# uC.net
KiCad netlist of a schematic drawn in Altium Designer
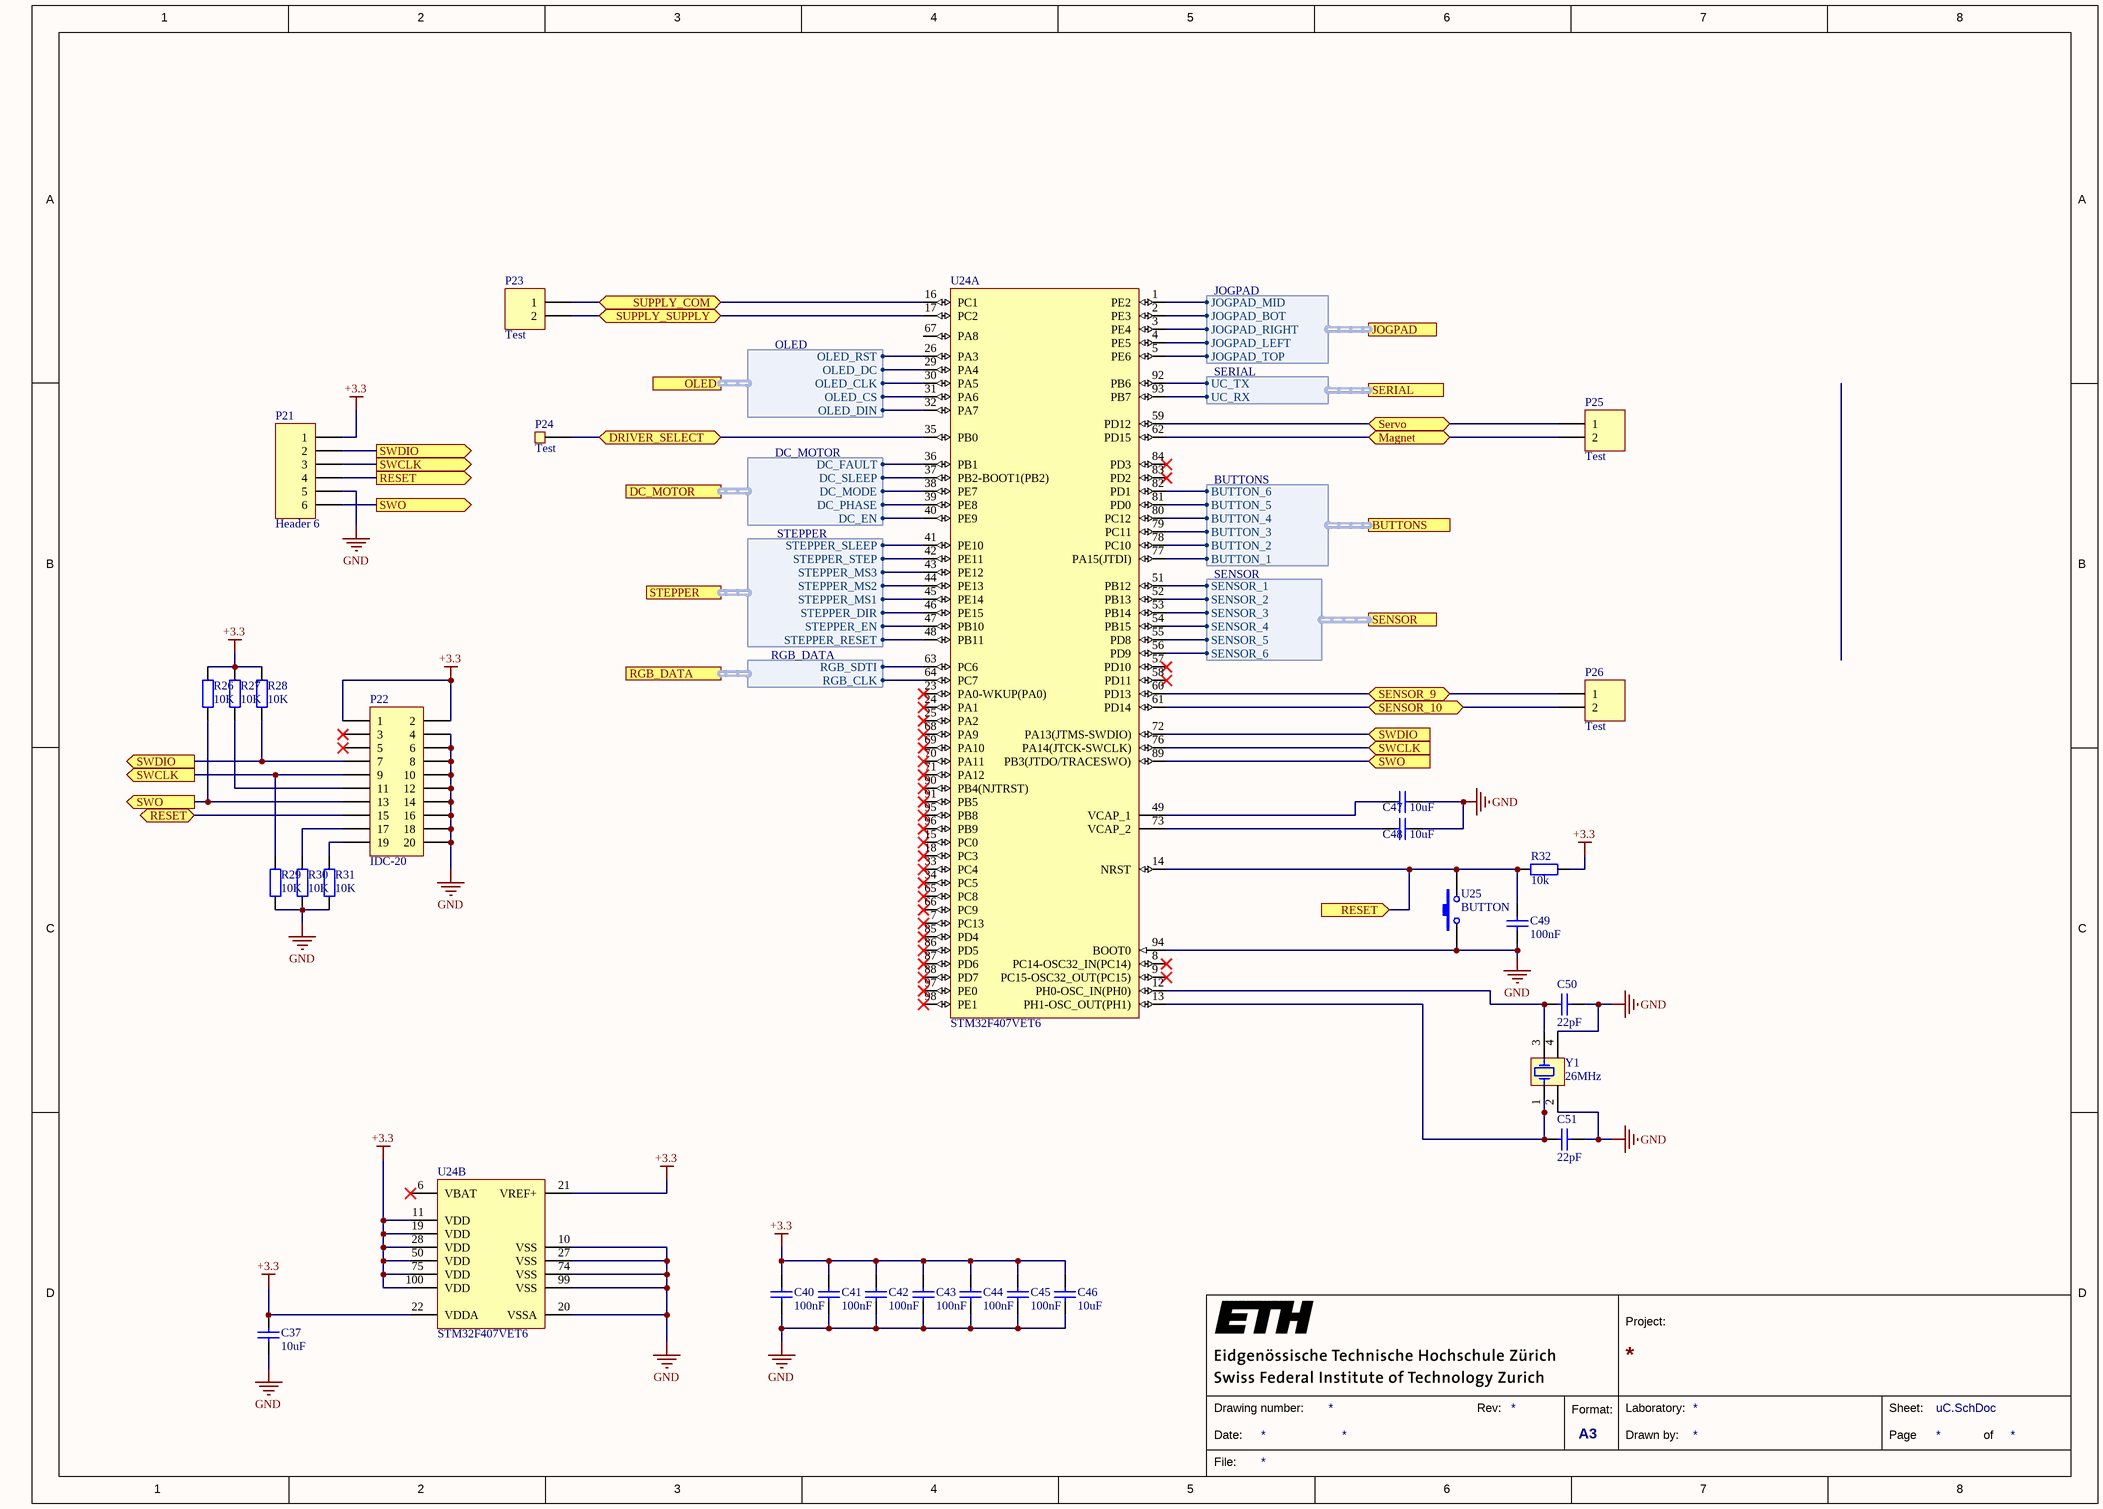
[diagram p0: uC.SchDoc]

(export (version "E")
  (design (tool "Eeschema 10.0.6"))
  (components
    (comp (ref "C37")
      (value "10uF")
      (footprint "CAP_0603i_1608m -N")
      (description "capacitor")
      (libsource (lib "IDSC std generic parts") (part "Cap"))
    )
    (comp (ref "C40")
      (value "100nF")
      (footprint "CAP_0402i_1005m -N")
      (description "capacitor")
      (libsource (lib "IDSC std generic parts") (part "Cap"))
    )
    (comp (ref "C41")
      (value "100nF")
      (footprint "CAP_0402i_1005m -N")
      (description "capacitor")
      (libsource (lib "IDSC std generic parts") (part "Cap"))
    )
    (comp (ref "C42")
      (value "100nF")
      (footprint "CAP_0402i_1005m -N")
      (description "capacitor")
      (libsource (lib "IDSC std generic parts") (part "Cap"))
    )
    (comp (ref "C43")
      (value "100nF")
      (footprint "CAP_0402i_1005m -N")
      (description "capacitor")
      (libsource (lib "IDSC std generic parts") (part "Cap"))
    )
    (comp (ref "C44")
      (value "100nF")
      (footprint "CAP_0402i_1005m -N")
      (description "capacitor")
      (libsource (lib "IDSC std generic parts") (part "Cap"))
    )
    (comp (ref "C45")
      (value "100nF")
      (footprint "CAP_0402i_1005m -N")
      (description "capacitor")
      (libsource (lib "IDSC std generic parts") (part "Cap"))
    )
    (comp (ref "C46")
      (value "10uF")
      (footprint "CAP_0603i_1608m -N")
      (description "capacitor")
      (libsource (lib "IDSC std generic parts") (part "Cap"))
    )
    (comp (ref "C47")
      (value "10uF")
      (footprint "CAP_0603i_1608m -N")
      (description "capacitor")
      (libsource (lib "IDSC std generic parts") (part "Cap"))
    )
    (comp (ref "C48")
      (value "10uF")
      (footprint "CAP_0603i_1608m -N")
      (description "capacitor")
      (libsource (lib "IDSC std generic parts") (part "Cap"))
    )
    (comp (ref "C49")
      (value "100nF")
      (footprint "CAP_0402i_1005m -N")
      (description "capacitor")
      (libsource (lib "IDSC std generic parts") (part "Cap"))
    )
    (comp (ref "C50")
      (value "22pF")
      (footprint "CAP_0603i_1608m -N")
      (description "capacitor")
      (libsource (lib "IDSC std generic parts") (part "Cap"))
    )
    (comp (ref "C51")
      (value "22pF")
      (footprint "CAP_0603i_1608m -N")
      (description "capacitor")
      (libsource (lib "IDSC std generic parts") (part "Cap"))
    )
    (comp (ref "P21")
      (value "Header 6")
      (footprint "HDR1X6")
      (description "Header, 6-Pin")
      (libsource (lib "IDSC std connectors") (part "Header 6"))
    )
    (comp (ref "P22")
      (value "IDC-20")
      (footprint "IDC-20")
      (description "Connector; IDC, Male Header, Thru-Hole; 20 Position; Vertical; Pitch 2.54 mm; B")
      (libsource (lib "IDSC std connectors") (part "IDC-20"))
    )
    (comp (ref "P23")
      (value "Test")
      (footprint "HDR1X2")
      (description "Header, 2-Pin")
      (libsource (lib "") (part "Header 2_1"))
    )
    (comp (ref "P24")
      (value "Test")
      (footprint "PIN1")
      (description "Single Pad or Testpoint")
      (libsource (lib "IDSC std connectors") (part "Pad"))
    )
    (comp (ref "P25")
      (value "Test")
      (footprint "HDR1X2")
      (description "Header, 2-Pin")
      (libsource (lib "IDSC std connectors") (part "Header 2"))
    )
    (comp (ref "P26")
      (value "Test")
      (footprint "HDR1X2")
      (description "Header, 2-Pin")
      (libsource (lib "IDSC std connectors") (part "Header 2"))
    )
    (comp (ref "R26")
      (value "10K")
      (footprint "RES_0603i_1608m -N")
      (description "Resistor")
      (libsource (lib "IDSC std generic parts") (part "Res"))
    )
    (comp (ref "R27")
      (value "10K")
      (footprint "RES_0603i_1608m -N")
      (description "Resistor")
      (libsource (lib "IDSC std generic parts") (part "Res"))
    )
    (comp (ref "R28")
      (value "10K")
      (footprint "RES_0603i_1608m -N")
      (description "Resistor")
      (libsource (lib "IDSC std generic parts") (part "Res"))
    )
    (comp (ref "R29")
      (value "10K")
      (footprint "RES_0603i_1608m -N")
      (description "Resistor")
      (libsource (lib "IDSC std generic parts") (part "Res"))
    )
    (comp (ref "R30")
      (value "10K")
      (footprint "RES_0603i_1608m -N")
      (description "Resistor")
      (libsource (lib "IDSC std generic parts") (part "Res"))
    )
    (comp (ref "R31")
      (value "10K")
      (footprint "RES_0603i_1608m -N")
      (description "Resistor")
      (libsource (lib "IDSC std generic parts") (part "Res"))
    )
    (comp (ref "R32")
      (value "10k")
      (footprint "RES_0603i_1608m -N")
      (description "Resistor")
      (libsource (lib "") (part "Res_1"))
    )
    (comp (ref "U24")
      (value "STM32F407VET6")
      (footprint "STM-LQFP100_M")
      (fields (field (name "MANUFACTURER") "STMicroelectronics"))
      (libsource (lib "Altium Content Vault") (part "MC-ARM-STM32F40X_41X-SQ100"))
    )
    (comp (ref "U25")
      (value "BUTTON")
      (footprint "RND 210-00206")
      (libsource (lib "BMA_lib") (part "BUTTON"))
    )
    (comp (ref "Y1")
      (value "26MHz")
      (footprint "TSX-3225 2*2.5")
      (description "Industrial Ceramic Resonator")
      (libsource (lib "IDSC std generic parts") (part "XTAL3"))
    )
  )
  (nets
    (net (code "9") (name "+3.3") (class "Default")
      (node (ref "C37") (pin "2") (pinfunction "2_2") (pintype "passive"))
      (node (ref "C40") (pin "1") (pinfunction "1_1") (pintype "passive"))
      (node (ref "C41") (pin "2") (pinfunction "2_2") (pintype "passive"))
      (node (ref "C42") (pin "2") (pinfunction "2_2") (pintype "passive"))
      (node (ref "C43") (pin "2") (pinfunction "2_2") (pintype "passive"))
      (node (ref "C44") (pin "2") (pinfunction "2_2") (pintype "passive"))
      (node (ref "C45") (pin "2") (pinfunction "2_2") (pintype "passive"))
      (node (ref "C46") (pin "2") (pinfunction "2_2") (pintype "passive"))
      (node (ref "P21") (pin "1") (pinfunction "1_1") (pintype "passive"))
      (node (ref "P22") (pin "1") (pinfunction "1_1") (pintype "passive"))
      (node (ref "P22") (pin "2") (pinfunction "2_2") (pintype "passive"))
      (node (ref "R26") (pin "2") (pinfunction "2_2") (pintype "passive"))
      (node (ref "R27") (pin "2") (pinfunction "2_2") (pintype "passive"))
      (node (ref "R28") (pin "2") (pinfunction "2_2") (pintype "passive"))
      (node (ref "R32") (pin "1") (pinfunction "1_1") (pintype "passive"))
      (node (ref "U24") (pin "100") (pinfunction "VDD_100") (pintype "power_in"))
      (node (ref "U24") (pin "11") (pinfunction "VDD_11") (pintype "power_in"))
      (node (ref "U24") (pin "19") (pinfunction "VDD_19") (pintype "power_in"))
      (node (ref "U24") (pin "21") (pinfunction "VREF+_21") (pintype "power_in"))
      (node (ref "U24") (pin "22") (pinfunction "VDDA_22") (pintype "power_in"))
      (node (ref "U24") (pin "28") (pinfunction "VDD_28") (pintype "power_in"))
      (node (ref "U24") (pin "50") (pinfunction "VDD_50") (pintype "power_in"))
      (node (ref "U24") (pin "75") (pinfunction "VDD_75") (pintype "power_in"))
    )
    (net (code "10") (name "/BUTTON_1") (class "Default")
      (node (ref "U24") (pin "77") (pinfunction "PA15(JTDI)_77") (pintype "bidirectional"))
    )
    (net (code "11") (name "/BUTTON_2") (class "Default")
      (node (ref "U24") (pin "78") (pinfunction "PC10_78") (pintype "bidirectional"))
    )
    (net (code "12") (name "/BUTTON_3") (class "Default")
      (node (ref "U24") (pin "79") (pinfunction "PC11_79") (pintype "bidirectional"))
    )
    (net (code "13") (name "/BUTTON_4") (class "Default")
      (node (ref "U24") (pin "80") (pinfunction "PC12_80") (pintype "bidirectional"))
    )
    (net (code "14") (name "/BUTTON_5") (class "Default")
      (node (ref "U24") (pin "81") (pinfunction "PD0_81") (pintype "bidirectional"))
    )
    (net (code "15") (name "/BUTTON_6") (class "Default")
      (node (ref "U24") (pin "82") (pinfunction "PD1_82") (pintype "bidirectional"))
    )
    (net (code "16") (name "/DC_EN") (class "Default")
      (node (ref "U24") (pin "40") (pinfunction "PE9_40") (pintype "bidirectional"))
    )
    (net (code "17") (name "/DC_FAULT") (class "Default")
      (node (ref "U24") (pin "36") (pinfunction "PB1_36") (pintype "bidirectional"))
    )
    (net (code "18") (name "/DC_MODE") (class "Default")
      (node (ref "U24") (pin "38") (pinfunction "PE7_38") (pintype "bidirectional"))
    )
    (net (code "19") (name "/DC_PHASE") (class "Default")
      (node (ref "U24") (pin "39") (pinfunction "PE8_39") (pintype "bidirectional"))
    )
    (net (code "20") (name "/DC_SLEEP") (class "Default")
      (node (ref "U24") (pin "37") (pinfunction "PB2-BOOT1(PB2)_37") (pintype "bidirectional"))
    )
    (net (code "21") (name "/DRIVER_SELECT") (class "Default")
      (node (ref "P24") (pin "1") (pinfunction "1_1") (pintype "passive"))
      (node (ref "U24") (pin "35") (pinfunction "PB0_35") (pintype "bidirectional"))
    )
    (net (code "22") (name "/JOGPAD_BOT") (class "Default")
      (node (ref "U24") (pin "2") (pinfunction "PE3_2") (pintype "bidirectional"))
    )
    (net (code "23") (name "/JOGPAD_LEFT") (class "Default")
      (node (ref "U24") (pin "4") (pinfunction "PE5_4") (pintype "bidirectional"))
    )
    (net (code "24") (name "/JOGPAD_MID") (class "Default")
      (node (ref "U24") (pin "1") (pinfunction "PE2_1") (pintype "bidirectional"))
    )
    (net (code "25") (name "/JOGPAD_RIGHT") (class "Default")
      (node (ref "U24") (pin "3") (pinfunction "PE4_3") (pintype "bidirectional"))
    )
    (net (code "26") (name "/JOGPAD_TOP") (class "Default")
      (node (ref "U24") (pin "5") (pinfunction "PE6_5") (pintype "bidirectional"))
    )
    (net (code "27") (name "/Magnet") (class "Default")
      (node (ref "P25") (pin "2") (pinfunction "2_2") (pintype "passive"))
      (node (ref "U24") (pin "62") (pinfunction "PD15_62") (pintype "bidirectional"))
    )
    (net (code "28") (name "/OLED_CLK") (class "Default")
      (node (ref "U24") (pin "30") (pinfunction "PA5_30") (pintype "bidirectional"))
    )
    (net (code "29") (name "/OLED_CS") (class "Default")
      (node (ref "U24") (pin "31") (pinfunction "PA6_31") (pintype "bidirectional"))
    )
    (net (code "30") (name "/OLED_DC") (class "Default")
      (node (ref "U24") (pin "29") (pinfunction "PA4_29") (pintype "bidirectional"))
    )
    (net (code "31") (name "/OLED_DIN") (class "Default")
      (node (ref "U24") (pin "32") (pinfunction "PA7_32") (pintype "bidirectional"))
    )
    (net (code "32") (name "/OLED_RST") (class "Default")
      (node (ref "U24") (pin "26") (pinfunction "PA3_26") (pintype "bidirectional"))
    )
    (net (code "33") (name "/RESET") (class "Default")
      (node (ref "C49") (pin "2") (pinfunction "2_2") (pintype "passive"))
      (node (ref "P21") (pin "4") (pinfunction "4_4") (pintype "passive"))
      (node (ref "P22") (pin "15") (pinfunction "15_15") (pintype "passive"))
      (node (ref "R32") (pin "2") (pinfunction "2_2") (pintype "passive"))
      (node (ref "U24") (pin "14") (pinfunction "NRST_14") (pintype "bidirectional"))
      (node (ref "U25") (pin "2") (pinfunction "2_2") (pintype "passive"))
    )
    (net (code "34") (name "/RGB_CLK") (class "Default")
      (node (ref "U24") (pin "64") (pinfunction "PC7_64") (pintype "bidirectional"))
    )
    (net (code "35") (name "/RGB_SDTI") (class "Default")
      (node (ref "U24") (pin "63") (pinfunction "PC6_63") (pintype "bidirectional"))
    )
    (net (code "36") (name "/SENSOR_1") (class "Default")
      (node (ref "U24") (pin "51") (pinfunction "PB12_51") (pintype "bidirectional"))
    )
    (net (code "37") (name "/SENSOR_2") (class "Default")
      (node (ref "U24") (pin "52") (pinfunction "PB13_52") (pintype "bidirectional"))
    )
    (net (code "38") (name "/SENSOR_3") (class "Default")
      (node (ref "U24") (pin "53") (pinfunction "PB14_53") (pintype "bidirectional"))
    )
    (net (code "39") (name "/SENSOR_4") (class "Default")
      (node (ref "U24") (pin "54") (pinfunction "PB15_54") (pintype "bidirectional"))
    )
    (net (code "40") (name "/SENSOR_5") (class "Default")
      (node (ref "U24") (pin "55") (pinfunction "PD8_55") (pintype "bidirectional"))
    )
    (net (code "41") (name "/SENSOR_6") (class "Default")
      (node (ref "U24") (pin "56") (pinfunction "PD9_56") (pintype "bidirectional"))
    )
    (net (code "42") (name "/SENSOR_9") (class "Default")
      (node (ref "P26") (pin "1") (pinfunction "1_1") (pintype "passive"))
      (node (ref "U24") (pin "60") (pinfunction "PD13_60") (pintype "bidirectional"))
    )
    (net (code "43") (name "/SENSOR_10") (class "Default")
      (node (ref "P26") (pin "2") (pinfunction "2_2") (pintype "passive"))
      (node (ref "U24") (pin "61") (pinfunction "PD14_61") (pintype "bidirectional"))
    )
    (net (code "44") (name "/STEPPER_DIR") (class "Default")
      (node (ref "U24") (pin "46") (pinfunction "PE15_46") (pintype "bidirectional"))
    )
    (net (code "45") (name "/STEPPER_EN") (class "Default")
      (node (ref "U24") (pin "47") (pinfunction "PB10_47") (pintype "bidirectional"))
    )
    (net (code "46") (name "/STEPPER_MS1") (class "Default")
      (node (ref "U24") (pin "45") (pinfunction "PE14_45") (pintype "bidirectional"))
    )
    (net (code "47") (name "/STEPPER_MS2") (class "Default")
      (node (ref "U24") (pin "44") (pinfunction "PE13_44") (pintype "bidirectional"))
    )
    (net (code "48") (name "/STEPPER_MS3") (class "Default")
      (node (ref "U24") (pin "43") (pinfunction "PE12_43") (pintype "bidirectional"))
    )
    (net (code "49") (name "/STEPPER_RESET") (class "Default")
      (node (ref "U24") (pin "48") (pinfunction "PB11_48") (pintype "bidirectional"))
    )
    (net (code "50") (name "/STEPPER_SLEEP") (class "Default")
      (node (ref "U24") (pin "41") (pinfunction "PE10_41") (pintype "bidirectional"))
    )
    (net (code "51") (name "/STEPPER_STEP") (class "Default")
      (node (ref "U24") (pin "42") (pinfunction "PE11_42") (pintype "bidirectional"))
    )
    (net (code "52") (name "/SUPPLY_COM") (class "Default")
      (node (ref "P23") (pin "1") (pinfunction "1_1") (pintype "passive"))
      (node (ref "U24") (pin "16") (pinfunction "PC1_16") (pintype "bidirectional"))
    )
    (net (code "53") (name "/SUPPLY_SUPPLY") (class "Default")
      (node (ref "P23") (pin "2") (pinfunction "2_2") (pintype "passive"))
      (node (ref "U24") (pin "17") (pinfunction "PC2_17") (pintype "bidirectional"))
    )
    (net (code "54") (name "/SWCLK") (class "Default")
      (node (ref "P21") (pin "3") (pinfunction "3_3") (pintype "passive"))
      (node (ref "P22") (pin "9") (pinfunction "9_9") (pintype "passive"))
      (node (ref "R29") (pin "2") (pinfunction "2_2") (pintype "passive"))
      (node (ref "U24") (pin "76") (pinfunction "PA14(JTCK-SWCLK)_76") (pintype "bidirectional"))
    )
    (net (code "55") (name "/SWDIO") (class "Default")
      (node (ref "P21") (pin "2") (pinfunction "2_2") (pintype "passive"))
      (node (ref "P22") (pin "7") (pinfunction "7_7") (pintype "passive"))
      (node (ref "R28") (pin "1") (pinfunction "1_1") (pintype "passive"))
      (node (ref "U24") (pin "72") (pinfunction "PA13(JTMS-SWDIO)_72") (pintype "bidirectional"))
    )
    (net (code "56") (name "/SWO") (class "Default")
      (node (ref "P21") (pin "6") (pinfunction "6_6") (pintype "passive"))
      (node (ref "P22") (pin "13") (pinfunction "13_13") (pintype "passive"))
      (node (ref "R26") (pin "1") (pinfunction "1_1") (pintype "passive"))
      (node (ref "U24") (pin "89") (pinfunction "PB3(JTDO/TRACESWO)_89") (pintype "bidirectional"))
    )
    (net (code "57") (name "/Servo") (class "Default")
      (node (ref "P25") (pin "1") (pinfunction "1_1") (pintype "passive"))
      (node (ref "U24") (pin "59") (pinfunction "PD12_59") (pintype "bidirectional"))
    )
    (net (code "58") (name "/UC_RX") (class "Default")
      (node (ref "U24") (pin "93") (pinfunction "PB7_93") (pintype "bidirectional"))
    )
    (net (code "59") (name "/UC_TX") (class "Default")
      (node (ref "U24") (pin "92") (pinfunction "PB6_92") (pintype "bidirectional"))
    )
    (net (code "68") (name "GND") (class "Default")
      (node (ref "C37") (pin "1") (pinfunction "1_1") (pintype "passive"))
      (node (ref "C40") (pin "2") (pinfunction "2_2") (pintype "passive"))
      (node (ref "C41") (pin "1") (pinfunction "1_1") (pintype "passive"))
      (node (ref "C42") (pin "1") (pinfunction "1_1") (pintype "passive"))
      (node (ref "C43") (pin "1") (pinfunction "1_1") (pintype "passive"))
      (node (ref "C44") (pin "1") (pinfunction "1_1") (pintype "passive"))
      (node (ref "C45") (pin "1") (pinfunction "1_1") (pintype "passive"))
      (node (ref "C46") (pin "1") (pinfunction "1_1") (pintype "passive"))
      (node (ref "C47") (pin "1") (pinfunction "1_1") (pintype "passive"))
      (node (ref "C48") (pin "1") (pinfunction "1_1") (pintype "passive"))
      (node (ref "C49") (pin "1") (pinfunction "1_1") (pintype "passive"))
      (node (ref "C50") (pin "1") (pinfunction "1_1") (pintype "passive"))
      (node (ref "C51") (pin "1") (pinfunction "1_1") (pintype "passive"))
      (node (ref "P21") (pin "5") (pinfunction "5_5") (pintype "passive"))
      (node (ref "P22") (pin "10") (pinfunction "10_10") (pintype "passive"))
      (node (ref "P22") (pin "12") (pinfunction "12_12") (pintype "passive"))
      (node (ref "P22") (pin "14") (pinfunction "14_14") (pintype "passive"))
      (node (ref "P22") (pin "16") (pinfunction "16_16") (pintype "passive"))
      (node (ref "P22") (pin "18") (pinfunction "18_18") (pintype "passive"))
      (node (ref "P22") (pin "20") (pinfunction "20_20") (pintype "passive"))
      (node (ref "P22") (pin "4") (pinfunction "4_4") (pintype "passive"))
      (node (ref "P22") (pin "6") (pinfunction "6_6") (pintype "passive"))
      (node (ref "P22") (pin "8") (pinfunction "8_8") (pintype "passive"))
      (node (ref "R29") (pin "1") (pinfunction "1_1") (pintype "passive"))
      (node (ref "R30") (pin "1") (pinfunction "1_1") (pintype "passive"))
      (node (ref "R31") (pin "1") (pinfunction "1_1") (pintype "passive"))
      (node (ref "U24") (pin "10") (pinfunction "VSS_10") (pintype "power_in"))
      (node (ref "U24") (pin "20") (pinfunction "VSSA_20") (pintype "power_in"))
      (node (ref "U24") (pin "27") (pinfunction "VSS_27") (pintype "power_in"))
      (node (ref "U24") (pin "74") (pinfunction "VSS_74") (pintype "power_in"))
      (node (ref "U24") (pin "94") (pinfunction "BOOT0_94") (pintype "input"))
      (node (ref "U24") (pin "99") (pinfunction "VSS_99") (pintype "power_in"))
      (node (ref "U25") (pin "1") (pinfunction "1_1") (pintype "passive"))
      (node (ref "Y1") (pin "2") (pinfunction "COM_2") (pintype "passive"))
      (node (ref "Y1") (pin "4") (pinfunction "COM_4") (pintype "passive"))
    )
    (net (code "69") (name "Net-(P22-Pad11)") (class "Default")
      (node (ref "P22") (pin "11") (pinfunction "11_11") (pintype "passive"))
      (node (ref "R27") (pin "1") (pinfunction "1_1") (pintype "passive"))
    )
    (net (code "70") (name "Net-(P22-Pad17)") (class "Default")
      (node (ref "P22") (pin "17") (pinfunction "17_17") (pintype "passive"))
      (node (ref "R30") (pin "2") (pinfunction "2_2") (pintype "passive"))
    )
    (net (code "71") (name "Net-(P22-Pad19)") (class "Default")
      (node (ref "P22") (pin "19") (pinfunction "19_19") (pintype "passive"))
      (node (ref "R31") (pin "2") (pinfunction "2_2") (pintype "passive"))
    )
    (net (code "72") (name "Net-(U24A-PH0-OSC_IN(PH0))") (class "Default")
      (node (ref "C50") (pin "2") (pinfunction "2_2") (pintype "passive"))
      (node (ref "U24") (pin "12") (pinfunction "PH0-OSC_IN(PH0)_12") (pintype "bidirectional"))
      (node (ref "Y1") (pin "3") (pinfunction "OSC2_3") (pintype "passive"))
    )
    (net (code "73") (name "Net-(U24A-PH1-OSC_OUT(PH1))") (class "Default")
      (node (ref "C51") (pin "2") (pinfunction "2_2") (pintype "passive"))
      (node (ref "U24") (pin "13") (pinfunction "PH1-OSC_OUT(PH1)_13") (pintype "bidirectional"))
      (node (ref "Y1") (pin "1") (pinfunction "OSC1_1") (pintype "passive"))
    )
    (net (code "74") (name "Net-(U24A-VCAP_1)") (class "Default")
      (node (ref "C47") (pin "2") (pinfunction "2_2") (pintype "passive"))
      (node (ref "U24") (pin "49") (pinfunction "VCAP_1_49") (pintype "power_in"))
    )
    (net (code "75") (name "Net-(U24A-VCAP_2)") (class "Default")
      (node (ref "C48") (pin "2") (pinfunction "2_2") (pintype "passive"))
      (node (ref "U24") (pin "73") (pinfunction "VCAP_2_73") (pintype "power_in"))
    )
    (net (code "76") (name "unconnected-(P22-Pad3)") (class "Default")
      (node (ref "P22") (pin "3") (pinfunction "3_3") (pintype "passive+no_connect"))
    )
    (net (code "77") (name "unconnected-(P22-Pad5)") (class "Default")
      (node (ref "P22") (pin "5") (pinfunction "5_5") (pintype "passive+no_connect"))
    )
    (net (code "78") (name "unconnected-(U24A-PA0-WKUP(PA0)-Pad23)") (class "Default")
      (node (ref "U24") (pin "23") (pinfunction "PA0-WKUP(PA0)_23") (pintype "bidirectional+no_connect"))
    )
    (net (code "79") (name "unconnected-(U24A-PA1-Pad24)") (class "Default")
      (node (ref "U24") (pin "24") (pinfunction "PA1_24") (pintype "bidirectional+no_connect"))
    )
    (net (code "80") (name "unconnected-(U24A-PA2-Pad25)") (class "Default")
      (node (ref "U24") (pin "25") (pinfunction "PA2_25") (pintype "bidirectional+no_connect"))
    )
    (net (code "81") (name "unconnected-(U24A-PA8-Pad67)") (class "Default")
      (node (ref "U24") (pin "67") (pinfunction "PA8_67") (pintype "bidirectional"))
    )
    (net (code "82") (name "unconnected-(U24A-PA9-Pad68)") (class "Default")
      (node (ref "U24") (pin "68") (pinfunction "PA9_68") (pintype "bidirectional+no_connect"))
    )
    (net (code "83") (name "unconnected-(U24A-PA10-Pad69)") (class "Default")
      (node (ref "U24") (pin "69") (pinfunction "PA10_69") (pintype "bidirectional+no_connect"))
    )
    (net (code "84") (name "unconnected-(U24A-PA11-Pad70)") (class "Default")
      (node (ref "U24") (pin "70") (pinfunction "PA11_70") (pintype "bidirectional+no_connect"))
    )
    (net (code "85") (name "unconnected-(U24A-PA12-Pad71)") (class "Default")
      (node (ref "U24") (pin "71") (pinfunction "PA12_71") (pintype "bidirectional+no_connect"))
    )
    (net (code "86") (name "unconnected-(U24A-PB4(NJTRST)-Pad90)") (class "Default")
      (node (ref "U24") (pin "90") (pinfunction "PB4(NJTRST)_90") (pintype "bidirectional+no_connect"))
    )
    (net (code "87") (name "unconnected-(U24A-PB5-Pad91)") (class "Default")
      (node (ref "U24") (pin "91") (pinfunction "PB5_91") (pintype "bidirectional+no_connect"))
    )
    (net (code "88") (name "unconnected-(U24A-PB8-Pad95)") (class "Default")
      (node (ref "U24") (pin "95") (pinfunction "PB8_95") (pintype "bidirectional+no_connect"))
    )
    (net (code "89") (name "unconnected-(U24A-PB9-Pad96)") (class "Default")
      (node (ref "U24") (pin "96") (pinfunction "PB9_96") (pintype "bidirectional+no_connect"))
    )
    (net (code "90") (name "unconnected-(U24A-PC0-Pad15)") (class "Default")
      (node (ref "U24") (pin "15") (pinfunction "PC0_15") (pintype "bidirectional+no_connect"))
    )
    (net (code "91") (name "unconnected-(U24A-PC3-Pad18)") (class "Default")
      (node (ref "U24") (pin "18") (pinfunction "PC3_18") (pintype "bidirectional+no_connect"))
    )
    (net (code "92") (name "unconnected-(U24A-PC4-Pad33)") (class "Default")
      (node (ref "U24") (pin "33") (pinfunction "PC4_33") (pintype "bidirectional+no_connect"))
    )
    (net (code "93") (name "unconnected-(U24A-PC5-Pad34)") (class "Default")
      (node (ref "U24") (pin "34") (pinfunction "PC5_34") (pintype "bidirectional+no_connect"))
    )
    (net (code "94") (name "unconnected-(U24A-PC8-Pad65)") (class "Default")
      (node (ref "U24") (pin "65") (pinfunction "PC8_65") (pintype "bidirectional+no_connect"))
    )
    (net (code "95") (name "unconnected-(U24A-PC9-Pad66)") (class "Default")
      (node (ref "U24") (pin "66") (pinfunction "PC9_66") (pintype "bidirectional+no_connect"))
    )
    (net (code "96") (name "unconnected-(U24A-PC13-Pad7)") (class "Default")
      (node (ref "U24") (pin "7") (pinfunction "PC13_7") (pintype "bidirectional+no_connect"))
    )
    (net (code "97") (name "unconnected-(U24A-PC14-OSC32_IN(PC14)-Pad8)") (class "Default")
      (node (ref "U24") (pin "8") (pinfunction "PC14-OSC32_IN(PC14)_8") (pintype "bidirectional+no_connect"))
    )
    (net (code "98") (name "unconnected-(U24A-PC15-OSC32_OUT(PC15)-Pad9)") (class "Default")
      (node (ref "U24") (pin "9") (pinfunction "PC15-OSC32_OUT(PC15)_9") (pintype "bidirectional+no_connect"))
    )
    (net (code "99") (name "unconnected-(U24A-PD2-Pad83)") (class "Default")
      (node (ref "U24") (pin "83") (pinfunction "PD2_83") (pintype "bidirectional+no_connect"))
    )
    (net (code "100") (name "unconnected-(U24A-PD3-Pad84)") (class "Default")
      (node (ref "U24") (pin "84") (pinfunction "PD3_84") (pintype "bidirectional+no_connect"))
    )
    (net (code "101") (name "unconnected-(U24A-PD4-Pad85)") (class "Default")
      (node (ref "U24") (pin "85") (pinfunction "PD4_85") (pintype "bidirectional+no_connect"))
    )
    (net (code "102") (name "unconnected-(U24A-PD5-Pad86)") (class "Default")
      (node (ref "U24") (pin "86") (pinfunction "PD5_86") (pintype "bidirectional+no_connect"))
    )
    (net (code "103") (name "unconnected-(U24A-PD6-Pad87)") (class "Default")
      (node (ref "U24") (pin "87") (pinfunction "PD6_87") (pintype "bidirectional+no_connect"))
    )
    (net (code "104") (name "unconnected-(U24A-PD7-Pad88)") (class "Default")
      (node (ref "U24") (pin "88") (pinfunction "PD7_88") (pintype "bidirectional+no_connect"))
    )
    (net (code "105") (name "unconnected-(U24A-PD10-Pad57)") (class "Default")
      (node (ref "U24") (pin "57") (pinfunction "PD10_57") (pintype "bidirectional+no_connect"))
    )
    (net (code "106") (name "unconnected-(U24A-PD11-Pad58)") (class "Default")
      (node (ref "U24") (pin "58") (pinfunction "PD11_58") (pintype "bidirectional+no_connect"))
    )
    (net (code "107") (name "unconnected-(U24A-PE0-Pad97)") (class "Default")
      (node (ref "U24") (pin "97") (pinfunction "PE0_97") (pintype "bidirectional+no_connect"))
    )
    (net (code "108") (name "unconnected-(U24A-PE1-Pad98)") (class "Default")
      (node (ref "U24") (pin "98") (pinfunction "PE1_98") (pintype "bidirectional+no_connect"))
    )
    (net (code "109") (name "unconnected-(U24B-VBAT-Pad6)") (class "Default")
      (node (ref "U24") (pin "6") (pinfunction "VBAT_6") (pintype "power_in+no_connect"))
    )
  )
)
